# LDO.net
KiCad netlist of a schematic drawn in Altium Designer
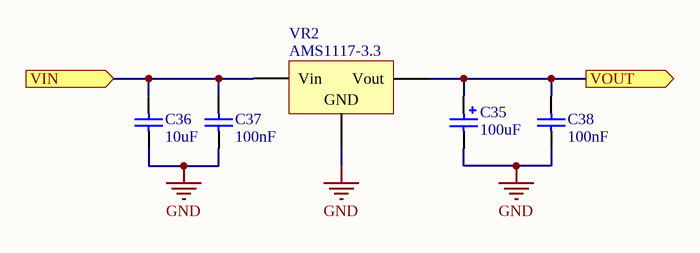
[diagram p0: LDO.SchDoc]

(export (version "E")
  (design (tool "Eeschema 10.0.6"))
  (components
    (comp (ref "C35")
      (value "100uF")
      (footprint "CASE-B_3528")
      (description "Tantalum capacitor")
      (fields (field (name "MANUFACTURER") "AVX") (field (name "PARTNUMBER") "TAJB107K006RNJ"))
      (libsource (lib "Cap") (part "3528 100uF (107) 10% 6.3V"))
    )
    (comp (ref "C36")
      (value "10uF")
      (footprint "1206_C")
      (description "Chip capacitors")
      (fields
        (field (name "MANUFACTURER") "Samsung Electro-Mechanics")
        (field (name "PARTNUMBER") "CL31A106KBHNNNE")
      )
      (libsource (lib "Cap") (part "1206 10uF (106) 10% 50V"))
    )
    (comp (ref "C37")
      (value "100nF")
      (footprint "0805_C")
      (description "Chip capacitors")
      (fields (field (name "MANUFACTURER") "YAGEO") (field (name "PARTNUMBER") "CC0805KRX7R9BB104"))
      (libsource (lib "Miscellaneous Devices LC") (part "0805 100nF(104) 10% 50V"))
    )
    (comp (ref "C38")
      (value "100nF")
      (footprint "1206_C")
      (description "Chip capacitors")
      (fields
        (field (name "MANUFACTURER") "Samsung Electro-Mechanics")
        (field (name "PARTNUMBER") "CL31B104KBCNNNC")
      )
      (libsource (lib "Miscellaneous Devices LC") (part "1206 100nF (104) 10% 50V"))
    )
    (comp (ref "VR2")
      (value "AMS1117-3.3")
      (footprint "SOT-223")
      (description "低压差线性稳压(LDO)")
      (libsource (lib "Miscellaneous Devices LC") (part "SOT-223 AMS1117-3.3"))
    )
  )
  (nets
    (net (code "1") (name "/VIN") (class "Default")
      (node (ref "C36") (pin "2") (pinfunction "2_2") (pintype "passive"))
      (node (ref "C37") (pin "2") (pinfunction "2_2") (pintype "passive"))
      (node (ref "VR2") (pin "3") (pinfunction "Vin_3") (pintype "passive"))
    )
    (net (code "2") (name "/VOUT") (class "Default")
      (node (ref "C35") (pin "1") (pinfunction "1_1") (pintype "passive"))
      (node (ref "C38") (pin "2") (pinfunction "2_2") (pintype "passive"))
      (node (ref "VR2") (pin "2") (pinfunction "Vout_2") (pintype "passive"))
    )
    (net (code "3") (name "GND") (class "Default")
      (node (ref "C35") (pin "2") (pinfunction "2_2") (pintype "passive"))
      (node (ref "C36") (pin "1") (pinfunction "1_1") (pintype "passive"))
      (node (ref "C37") (pin "1") (pinfunction "1_1") (pintype "passive"))
      (node (ref "C38") (pin "1") (pinfunction "1_1") (pintype "passive"))
      (node (ref "VR2") (pin "1") (pinfunction "GND_1") (pintype "passive"))
    )
  )
)
